# bolid-power-input.net
KiCad netlist of a schematic drawn in Altium Designer
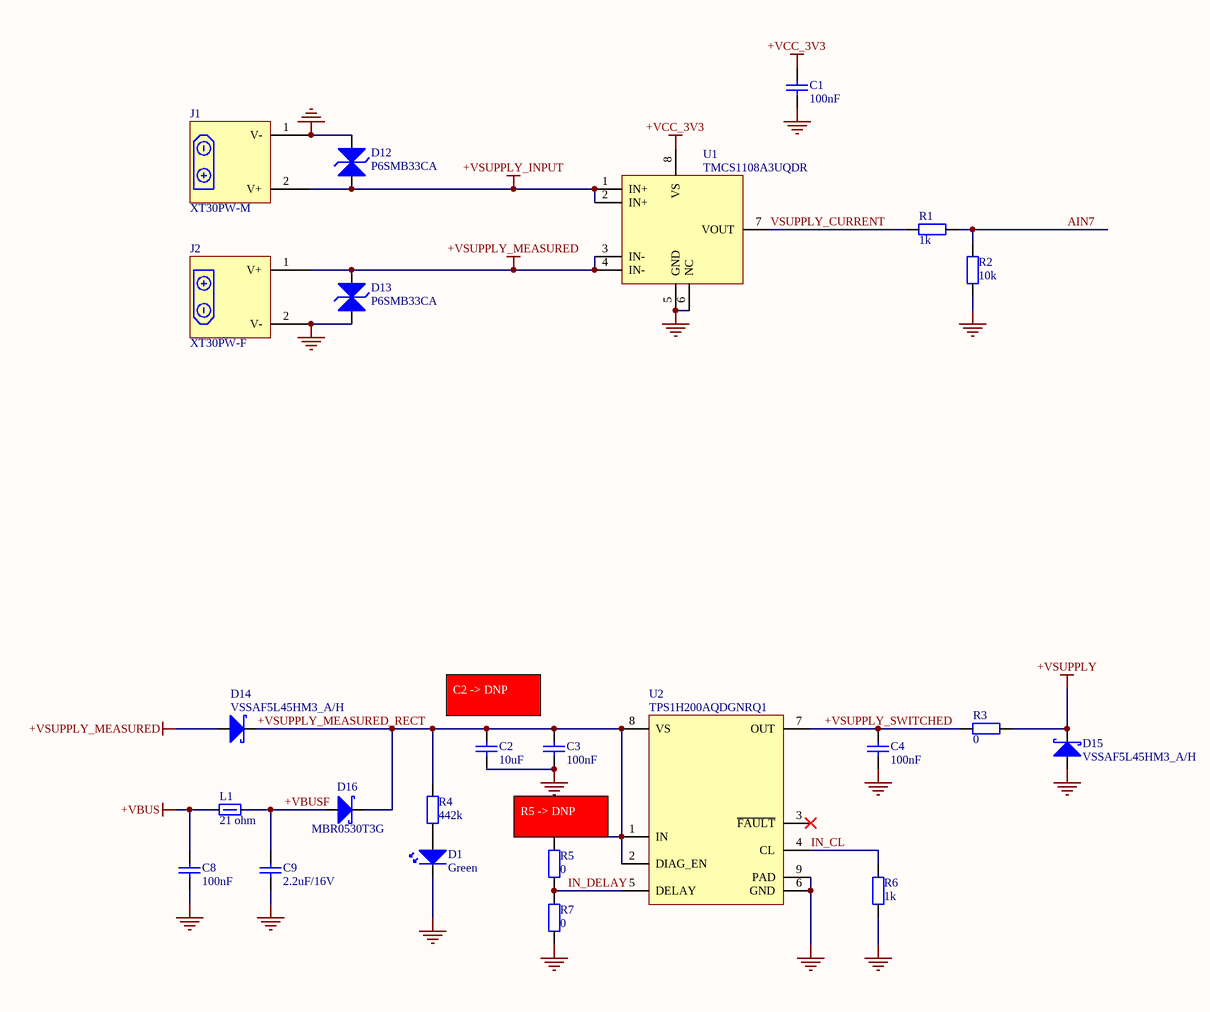
[diagram p0: bolid-power-input.SchDoc]

(export (version "E")
  (design (tool "Eeschema 10.0.6"))
  (components
    (comp (ref "C1")
      (value "GRM155R71H104KE14D")
      (footprint "C0402-CAPC100X50X55L22 - Tayio Yuden TDK")
      (description "MLCC 0402 (1005) 100nF 10% 50V X7R")
      (fields
        (field (name "MANUFACTURER") "Murata Electronics")
        (field (name "TOLERANCE") "10 %")
        (field (name "VALUE DISPLAYED") "100nF")
      )
      (libsource (lib "capacitors2") (part "GRM155R71H104KE14D"))
    )
    (comp (ref "C2")
      (value "C1210C106K5RACTU")
      (footprint "C1210-CAPC320X250X280L55N - Kemet")
      (description "MLCC 1210 (3225) 10uF 10% 50V X7R")
      (fields
        (field (name "MANUFACTURER") "KEMET")
        (field (name "TOLERANCE") "10 %")
        (field (name "VALUE DISPLAYED") "10uF")
      )
      (libsource (lib "capacitors2") (part "C1210C106K5RACTU"))
    )
    (comp (ref "C3")
      (value "GRM155R71H104KE14D")
      (footprint "C0402-CAPC100X50X55L22 - Tayio Yuden TDK")
      (description "MLCC 0402 (1005) 100nF 10% 50V X7R")
      (fields
        (field (name "MANUFACTURER") "Murata Electronics")
        (field (name "TOLERANCE") "10 %")
        (field (name "VALUE DISPLAYED") "100nF")
      )
      (libsource (lib "capacitors2") (part "GRM155R71H104KE14D"))
    )
    (comp (ref "C4")
      (value "GRM155R71H104KE14D")
      (footprint "C0402-CAPC100X50X55L22 - Tayio Yuden TDK")
      (description "MLCC 0402 (1005) 100nF 10% 50V X7R")
      (fields
        (field (name "MANUFACTURER") "Murata Electronics")
        (field (name "TOLERANCE") "10 %")
        (field (name "VALUE DISPLAYED") "100nF")
      )
      (libsource (lib "capacitors2") (part "GRM155R71H104KE14D"))
    )
    (comp (ref "C8")
      (value "GRM155R71H104KE14D")
      (footprint "C0402-CAPC100X50X55L22 - Tayio Yuden TDK")
      (description "MLCC 0402 (1005) 100nF 10% 50V X7R")
      (fields
        (field (name "MANUFACTURER") "Murata Electronics")
        (field (name "TOLERANCE") "10 %")
        (field (name "VALUE DISPLAYED") "100nF")
      )
      (libsource (lib "capacitors2") (part "GRM155R71H104KE14D"))
    )
    (comp (ref "C9")
      (value "EMK107BB7225MA-T")
      (footprint "C0603-CAPC162X80X95L35N")
      (description "MLCC 0603 (1608) 2.2uF 20% 16V X7R")
      (fields
        (field (name "MANUFACTURER") "Taiyo Yuden")
        (field (name "TOLERANCE") "20 %")
        (field (name "VALUE DISPLAYED") "2.2uF/16V")
      )
      (libsource (lib "capacitors2") (part "EMK107BB7225MA-T"))
    )
    (comp (ref "D1")
      (value "150060GS75000")
      (footprint "D0603 DIONC166X84X36L42N Littelfuse")
      (description "LED 0603 (1608) Green")
      (fields (field (name "MANUFACTURER") "Wurth Elektronik") (field (name "ILLUMINATION COLOR") "Green"))
      (libsource (lib "semiconductors2") (part "150060GS75000"))
    )
    (comp (ref "D12")
      (value "P6SMB33CA")
      (footprint "DO-214AA SMB BIPOLAR DIOM540X362X261L115X205N - Littlefuse")
      (description "TVS DIODE 28.2VWM 45.7VC SMD")
      (fields (field (name "MANUFACTURER") "Littelfuse"))
      (libsource (lib "semiconductors2") (part "P6SMB33CA"))
    )
    (comp (ref "D13")
      (value "P6SMB33CA")
      (footprint "DO-214AA SMB BIPOLAR DIOM540X362X261L115X205N - Littlefuse")
      (description "TVS DIODE 28.2VWM 45.7VC SMD")
      (fields (field (name "MANUFACTURER") "Littelfuse"))
      (libsource (lib "semiconductors2") (part "P6SMB33CA"))
    )
    (comp (ref "D14")
      (value "VSSAF5L45HM3_A/H")
      (footprint "DO-221AC SlimSMA SODFL520X260X100L97X135N - Vishay")
      (description "Schottky Rectifier Diode, 5A, Do-221Ac-2 Rohs Compliant: Yes ¦Vishay VSSAF5L45HM3_A/H")
      (fields (field (name "MANUFACTURER") "Vishay"))
      (libsource (lib "semiconductors2") (part "VSSAF5L45HM3_A/H"))
    )
    (comp (ref "D15")
      (value "VSSAF5L45HM3_A/H")
      (footprint "DO-221AC SlimSMA SODFL520X260X100L97X135N - Vishay")
      (description "Schottky Rectifier Diode, 5A, Do-221Ac-2 Rohs Compliant: Yes ¦Vishay VSSAF5L45HM3_A/H")
      (fields (field (name "MANUFACTURER") "Vishay"))
      (libsource (lib "semiconductors2") (part "VSSAF5L45HM3_A/H"))
    )
    (comp (ref "D16")
      (value "MBR0530T3G")
      (footprint "SOD-123-2L SOD375X160X128L32X60N - Fairchild")
      (description "ON Semi MBR0530T3G; SMT Schottky Diode; 30V 500mA; 2-Pin SOD-123")
      (fields (field (name "MANUFACTURER") "ON Semiconductor"))
      (libsource (lib "semiconductors2") (part "MBR0530T3G"))
    )
    (comp (ref "J1")
      (value "XT30PW-M")
      (footprint "AMASS XT30PW-M")
      (libsource (lib "connectors2") (part "XT30PW-M"))
    )
    (comp (ref "J2")
      (value "XT30PW-F")
      (footprint "AMASS XT30PW-F")
      (libsource (lib "connectors2") (part "XT30PW-F"))
    )
    (comp (ref "L1")
      (value "21 ohm")
      (footprint "FB0805 - BEADC205X125X145L50N")
      (description "Ferrite Beads Power Chip 21Ohm 30% 100MHz 6A 0.004Ohm DCR 0805 Automotive T/R")
      (fields
        (field (name "MANUFACTURER") "Taiyo Yuden")
        (field (name "MANUFACTURER PART NUMBER") "FBMJ2125HM210NT")
      )
      (libsource (lib "inductors2") (part "FBMJ2125HM210NT"))
    )
    (comp (ref "R1")
      (value "1k")
      (footprint "R0402-RESC100X50X40L22N")
      (description "RES 0402 (1005) 1.00k 1% 0.0625W 50V Thick Film")
      (fields
        (field (name "MANUFACTURER") "Yageo")
        (field (name "MANUFACTURER PART NUMBER") "RC0402FR-071KL")
      )
      (libsource (lib "") (part "RC0402FR-071KL_1"))
    )
    (comp (ref "R2")
      (value "10k")
      (footprint "R0402-RESC100X50X40L22N")
      (description "RES 0402 (1005) 10.0k 1% 0.0625W 50V Thick Film")
      (fields
        (field (name "MANUFACTURER") "Yageo")
        (field (name "MANUFACTURER PART NUMBER") "RC0402FR-0710KL")
      )
      (libsource (lib "resistors2") (part "RC0402FR-0710KL"))
    )
    (comp (ref "R3")
      (value "0")
      (footprint "R1206-RESC307X157X65L40N")
      (description "RES 1206 (3216) 0.00 ohm 1% 0.250W Thick Film")
      (fields
        (field (name "MANUFACTURER") "Yageo")
        (field (name "MANUFACTURER PART NUMBER") "AC1206JR-130RL")
      )
      (libsource (lib "resistors2") (part "AC1206JR-130RL"))
    )
    (comp (ref "R4")
      (value "442k")
      (footprint "R0402-RESC100X50X40L22N")
      (description "RES 0402 (1005) 442.0k 1% 0.100W 50V Thick Film")
      (fields
        (field (name "MANUFACTURER") "Panasonic")
        (field (name "MANUFACTURER PART NUMBER") "ERJ-2RKF4423X")
      )
      (libsource (lib "resistors2") (part "ERJ-2RKF4423X"))
    )
    (comp (ref "R5")
      (value "0")
      (footprint "R0402-RESC100X50X40L22N")
      (description "RES 0402 (1005) 0.00 ohm 1% 0.0625W 50V Thick Film")
      (fields
        (field (name "MANUFACTURER") "Yageo")
        (field (name "MANUFACTURER PART NUMBER") "RC0402JR-7D0RL")
      )
      (libsource (lib "resistors2") (part "RC0402JR-7D0RL"))
    )
    (comp (ref "R6")
      (value "1k")
      (footprint "R0402-RESC100X50X40L22N")
      (description "RES 0402 (1005) 1.00k 1% 0.0625W 50V Thick Film")
      (fields
        (field (name "MANUFACTURER") "Yageo")
        (field (name "MANUFACTURER PART NUMBER") "RC0402FR-071KL")
      )
      (libsource (lib "resistors2") (part "RC0402FR-071KL"))
    )
    (comp (ref "R7")
      (value "0")
      (footprint "R0402-RESC100X50X40L22N")
      (description "RES 0402 (1005) 0.00 ohm 1% 0.0625W 50V Thick Film")
      (fields
        (field (name "MANUFACTURER") "Yageo")
        (field (name "MANUFACTURER PART NUMBER") "RC0402JR-7D0RL")
      )
      (libsource (lib "resistors2") (part "RC0402JR-7D0RL"))
    )
    (comp (ref "U1")
      (value "TMCS1108A3UQDR")
      (footprint "TI SOIC8 D0008B SOIC127P600X175-8N")
      (description "100-V Hall-effect current sensor with internal reference 8-SOIC -40 to 85")
      (fields (field (name "MANUFACTURER") "Texas Instruments"))
      (libsource (lib "ics2") (part "TMCS1108A3UQDR"))
    )
    (comp (ref "U2")
      (value "TPS1H200AQDGNRQ1")
      (footprint "TI VSSOP8 DGN0008G TSOP65P490X110_HS-9N")
      (description "Power switch IC-Power distribution: 3.4-40V; -40+125 st.C; SMD; MSOP-PowerPad-8; AEC-Q100")
      (fields (field (name "MANUFACTURER") "Texas Instruments"))
      (libsource (lib "ics2") (part "TPS1H200AQDGNRQ1"))
    )
  )
  (nets
    (net (code "1") (name "+VBUS") (class "Default")
      (node (ref "C8") (pin "2") (pinfunction "2_2") (pintype "passive"))
      (node (ref "L1") (pin "1") (pinfunction "1_1") (pintype "passive"))
    )
    (net (code "2") (name "+VCC_3V3") (class "Default")
      (node (ref "C1") (pin "2") (pinfunction "2_2") (pintype "passive"))
      (node (ref "U1") (pin "8") (pinfunction "VS_8") (pintype "passive"))
    )
    (net (code "3") (name "+VSUPPLY") (class "Default")
      (node (ref "D15") (pin "1") (pinfunction "K_1") (pintype "passive"))
      (node (ref "R3") (pin "2") (pinfunction "2_2") (pintype "passive"))
    )
    (net (code "4") (name "+VSUPPLY_INPUT") (class "Default")
      (node (ref "D12") (pin "1") (pinfunction "1_1") (pintype "passive"))
      (node (ref "J1") (pin "2") (pinfunction "V+_2") (pintype "passive"))
      (node (ref "U1") (pin "1") (pinfunction "IN+_1") (pintype "passive"))
      (node (ref "U1") (pin "2") (pinfunction "IN+_2") (pintype "passive"))
    )
    (net (code "5") (name "+VSUPPLY_MEASURED") (class "Default")
      (node (ref "D13") (pin "2") (pinfunction "2_2") (pintype "passive"))
      (node (ref "D14") (pin "2") (pinfunction "A_2") (pintype "passive"))
      (node (ref "J2") (pin "1") (pinfunction "V+_1") (pintype "passive"))
      (node (ref "U1") (pin "3") (pinfunction "IN-_3") (pintype "passive"))
      (node (ref "U1") (pin "4") (pinfunction "IN-_4") (pintype "passive"))
    )
    (net (code "6") (name "/+VBUSF") (class "Default")
      (node (ref "C9") (pin "2") (pinfunction "2_2") (pintype "passive"))
      (node (ref "D16") (pin "2") (pinfunction "A_2") (pintype "passive"))
      (node (ref "L1") (pin "2") (pinfunction "2_2") (pintype "passive"))
    )
    (net (code "7") (name "/+VSUPPLY_MEASURED_RECT") (class "Default")
      (node (ref "C2") (pin "2") (pinfunction "2_2") (pintype "passive"))
      (node (ref "C3") (pin "2") (pinfunction "2_2") (pintype "passive"))
      (node (ref "D14") (pin "1") (pinfunction "K_1") (pintype "passive"))
      (node (ref "D16") (pin "1") (pinfunction "K_1") (pintype "passive"))
      (node (ref "R4") (pin "2") (pinfunction "2_2") (pintype "passive"))
      (node (ref "R5") (pin "1") (pinfunction "1_1") (pintype "passive"))
      (node (ref "U2") (pin "1") (pinfunction "IN_1") (pintype "passive"))
      (node (ref "U2") (pin "2") (pinfunction "DIAG_EN_2") (pintype "passive"))
      (node (ref "U2") (pin "8") (pinfunction "VS_8") (pintype "passive"))
    )
    (net (code "8") (name "/+VSUPPLY_SWITCHED") (class "Default")
      (node (ref "C4") (pin "2") (pinfunction "2_2") (pintype "passive"))
      (node (ref "R3") (pin "1") (pinfunction "1_1") (pintype "passive"))
      (node (ref "U2") (pin "7") (pinfunction "OUT_7") (pintype "passive"))
    )
    (net (code "9") (name "/AIN7") (class "Default")
      (node (ref "R1") (pin "1") (pinfunction "1_1") (pintype "passive"))
      (node (ref "R2") (pin "2") (pinfunction "2_2") (pintype "passive"))
    )
    (net (code "10") (name "/IN_CL") (class "Default")
      (node (ref "R6") (pin "2") (pinfunction "2_2") (pintype "passive"))
      (node (ref "U2") (pin "4") (pinfunction "CL_4") (pintype "passive"))
    )
    (net (code "11") (name "/IN_DELAY") (class "Default")
      (node (ref "R5") (pin "2") (pinfunction "2_2") (pintype "passive"))
      (node (ref "R7") (pin "1") (pinfunction "1_1") (pintype "passive"))
      (node (ref "U2") (pin "5") (pinfunction "DELAY_5") (pintype "passive"))
    )
    (net (code "12") (name "/VSUPPLY_CURRENT") (class "Default")
      (node (ref "R1") (pin "2") (pinfunction "2_2") (pintype "passive"))
      (node (ref "U1") (pin "7") (pinfunction "VOUT_7") (pintype "passive"))
    )
    (net (code "13") (name "GND") (class "Default")
      (node (ref "C1") (pin "1") (pinfunction "1_1") (pintype "passive"))
      (node (ref "C2") (pin "1") (pinfunction "1_1") (pintype "passive"))
      (node (ref "C3") (pin "1") (pinfunction "1_1") (pintype "passive"))
      (node (ref "C4") (pin "1") (pinfunction "1_1") (pintype "passive"))
      (node (ref "C8") (pin "1") (pinfunction "1_1") (pintype "passive"))
      (node (ref "C9") (pin "1") (pinfunction "1_1") (pintype "passive"))
      (node (ref "D1") (pin "1") (pinfunction "K_1") (pintype "passive"))
      (node (ref "D12") (pin "2") (pinfunction "2_2") (pintype "passive"))
      (node (ref "D13") (pin "1") (pinfunction "1_1") (pintype "passive"))
      (node (ref "D15") (pin "2") (pinfunction "A_2") (pintype "passive"))
      (node (ref "J1") (pin "1") (pinfunction "V-_1") (pintype "passive"))
      (node (ref "J2") (pin "2") (pinfunction "V-_2") (pintype "passive"))
      (node (ref "R2") (pin "1") (pinfunction "1_1") (pintype "passive"))
      (node (ref "R6") (pin "1") (pinfunction "1_1") (pintype "passive"))
      (node (ref "R7") (pin "2") (pinfunction "2_2") (pintype "passive"))
      (node (ref "U1") (pin "5") (pinfunction "GND_5") (pintype "passive"))
      (node (ref "U1") (pin "6") (pinfunction "NC_6") (pintype "passive"))
      (node (ref "U2") (pin "6") (pinfunction "GND_6") (pintype "passive"))
      (node (ref "U2") (pin "9") (pinfunction "PAD_9") (pintype "passive"))
    )
    (net (code "14") (name "Net-(D1-A)") (class "Default")
      (node (ref "D1") (pin "2") (pinfunction "A_2") (pintype "passive"))
      (node (ref "R4") (pin "1") (pinfunction "1_1") (pintype "passive"))
    )
    (net (code "15") (name "unconnected-(U2-~{FAULT}-Pad3)") (class "Default")
      (node (ref "U2") (pin "3") (pinfunction "~{FAULT}_3") (pintype "passive+no_connect"))
    )
  )
)
